# d11toy2.net
KiCad netlist of a schematic drawn in EAGLE
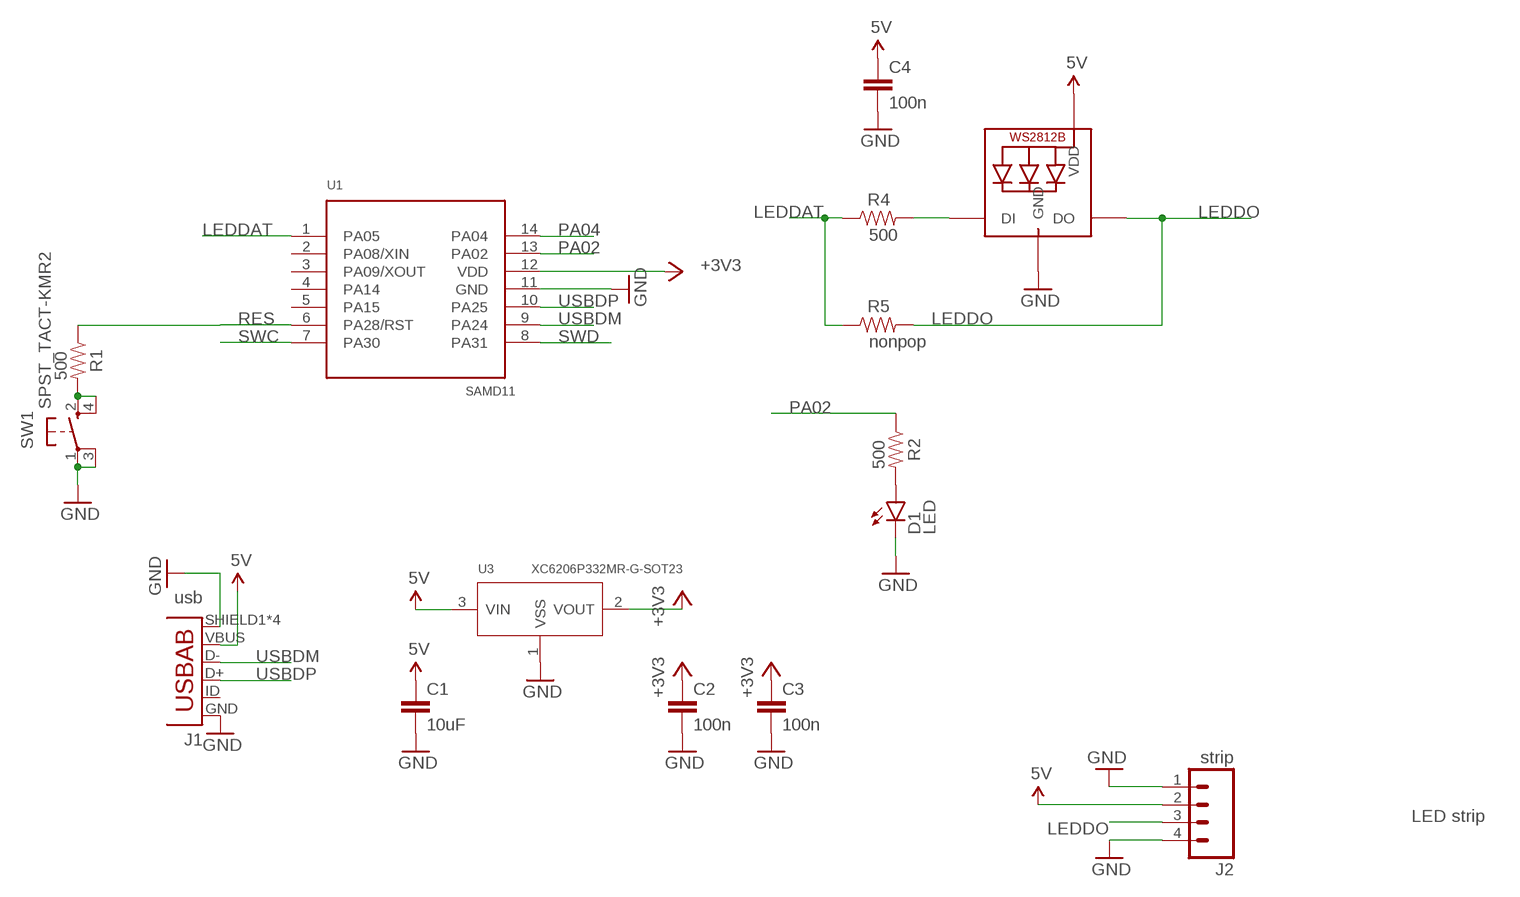
[diagram p0: schematic, sheet 1]

(export (version "E")
  (design (tool "Eeschema 10.0.6"))
  (components
    (comp (ref "C1")
      (value "10uF")
      (footprint "eagle-import:0603-CAP")
      (libsource (lib "eagle-import") (part "CAP0603-CAP"))
    )
    (comp (ref "C2")
      (value "100n")
      (footprint "eagle-import:0603-CAP")
      (libsource (lib "eagle-import") (part "CAP0603-CAP"))
    )
    (comp (ref "C3")
      (value "100n")
      (footprint "eagle-import:0603-CAP")
      (libsource (lib "eagle-import") (part "CAP0603-CAP"))
    )
    (comp (ref "C4")
      (value "100n")
      (footprint "eagle-import:0603-CAP")
      (libsource (lib "eagle-import") (part "CAP0603-CAP"))
    )
    (comp (ref "D1")
      (value "LED")
      (footprint "eagle-import:LED-0603")
      (libsource (lib "eagle-import") (part "LED0603"))
    )
    (comp (ref "J1")
      (value "usb")
      (footprint "eagle-import:USB-AB-MICRO-SMD")
      (libsource (lib "eagle-import") (part "USB-AB"))
    )
    (comp (ref "J2")
      (value "strip")
      (footprint "eagle-import:1X04_NO_SILK_ALL_ROUND")
      (libsource (lib "eagle-import") (part "M04NO_SILK_ALL_ROUND"))
    )
    (comp (ref "LED1")
      (value "WS2812B5050")
      (footprint "eagle-import:WS2812B")
      (libsource (lib "eagle-import") (part "WS2812B5050"))
    )
    (comp (ref "R1")
      (value "500")
      (footprint "eagle-import:0603-RES")
      (libsource (lib "eagle-import") (part "RESISTOR0603-RES"))
    )
    (comp (ref "R2")
      (value "500")
      (footprint "eagle-import:0603-RES")
      (libsource (lib "eagle-import") (part "RESISTOR0603-RES"))
    )
    (comp (ref "R4")
      (value "500")
      (footprint "eagle-import:0603-RES")
      (libsource (lib "eagle-import") (part "RESISTOR0603-RES"))
    )
    (comp (ref "R5")
      (value "nonpop")
      (footprint "eagle-import:0603-RES")
      (libsource (lib "eagle-import") (part "RESISTOR0603-RES"))
    )
    (comp (ref "SW1")
      (value "SPST_TACT-KMR2")
      (footprint "eagle-import:KMR2")
      (libsource (lib "eagle-import") (part "SPST_TACT-KMR2"))
    )
    (comp (ref "U1")
      (value "SAMD11")
      (footprint "eagle-import:SO14")
      (libsource (lib "eagle-import") (part "SAMD11C14"))
    )
    (comp (ref "U3")
      (value "XC6206P332MR-G-SOT23")
      (footprint "eagle-import:SOT-23")
      (fields (field (name "MPN") "XC6206P332MR-G"))
      (libsource (lib "eagle-import") (part "PMIC-LDO-XC6206P332MR-G(SOT23)"))
    )
  )
  (nets
    (net (code "1") (name "+3V3") (class "Default")
      (node (ref "C2") (pin "1") (pinfunction "1_1") (pintype "passive"))
      (node (ref "C3") (pin "1") (pinfunction "1_1") (pintype "passive"))
      (node (ref "U1") (pin "12") (pinfunction "VDD_12") (pintype "bidirectional"))
      (node (ref "U3") (pin "2") (pinfunction "VOUT_2") (pintype "output"))
    )
    (net (code "2") (name "/LEDDAT") (class "Default")
      (node (ref "R4") (pin "1") (pinfunction "1_1") (pintype "passive"))
      (node (ref "R5") (pin "1") (pinfunction "1_1") (pintype "passive"))
      (node (ref "U1") (pin "1") (pinfunction "PA05_1") (pintype "bidirectional"))
    )
    (net (code "3") (name "/LEDDO") (class "Default")
      (node (ref "J2") (pin "3") (pinfunction "3_3") (pintype "passive"))
      (node (ref "LED1") (pin "2-DOUT") (pinfunction "DO_2-DOUT") (pintype "output"))
      (node (ref "R5") (pin "2") (pinfunction "2_2") (pintype "passive"))
    )
    (net (code "4") (name "/PA02") (class "Default")
      (node (ref "R2") (pin "1") (pinfunction "1_1") (pintype "passive"))
      (node (ref "U1") (pin "13") (pinfunction "PA02_13") (pintype "bidirectional"))
    )
    (net (code "5") (name "/PA04") (class "Default")
      (node (ref "U1") (pin "14") (pinfunction "PA04_14") (pintype "bidirectional"))
    )
    (net (code "6") (name "/RES") (class "Default")
      (node (ref "R1") (pin "1") (pinfunction "1_1") (pintype "passive"))
      (node (ref "U1") (pin "6") (pinfunction "PA28/RST_6") (pintype "bidirectional"))
    )
    (net (code "7") (name "/SWC") (class "Default")
      (node (ref "U1") (pin "7") (pinfunction "PA30_7") (pintype "bidirectional"))
    )
    (net (code "8") (name "/SWD") (class "Default")
      (node (ref "U1") (pin "8") (pinfunction "PA31_8") (pintype "bidirectional"))
    )
    (net (code "9") (name "/USBDM") (class "Default")
      (node (ref "J1") (pin "D-") (pinfunction "D-_D-") (pintype "bidirectional"))
      (node (ref "U1") (pin "9") (pinfunction "PA24_9") (pintype "bidirectional"))
    )
    (net (code "10") (name "/USBDP") (class "Default")
      (node (ref "J1") (pin "D+") (pinfunction "D+_D+") (pintype "bidirectional"))
      (node (ref "U1") (pin "10") (pinfunction "PA25_10") (pintype "bidirectional"))
    )
    (net (code "11") (name "5V") (class "Default")
      (node (ref "C1") (pin "1") (pinfunction "1_1") (pintype "passive"))
      (node (ref "C4") (pin "1") (pinfunction "1_1") (pintype "passive"))
      (node (ref "J1") (pin "VBUS") (pinfunction "VBUS_VBUS") (pintype "bidirectional"))
      (node (ref "J2") (pin "2") (pinfunction "2_2") (pintype "passive"))
      (node (ref "LED1") (pin "1-VDD") (pinfunction "VDD_1-VDD") (pintype "power_in"))
      (node (ref "U3") (pin "3") (pinfunction "VIN_3") (pintype "input"))
    )
    (net (code "12") (name "GND") (class "Default")
      (node (ref "C1") (pin "2") (pinfunction "2_2") (pintype "passive"))
      (node (ref "C2") (pin "2") (pinfunction "2_2") (pintype "passive"))
      (node (ref "C3") (pin "2") (pinfunction "2_2") (pintype "passive"))
      (node (ref "C4") (pin "2") (pinfunction "2_2") (pintype "passive"))
      (node (ref "D1") (pin "C") (pinfunction "C_C") (pintype "passive"))
      (node (ref "J1") (pin "GND") (pinfunction "GND_GND") (pintype "bidirectional"))
      (node (ref "J1") (pin "SHIELD1") (pinfunction "SHIELD_SHIELD1") (pintype "bidirectional"))
      (node (ref "J1") (pin "SHIELD2") (pinfunction "SHIELD_SHIELD2") (pintype "bidirectional"))
      (node (ref "J1") (pin "SHIELD3") (pinfunction "SHIELD_SHIELD3") (pintype "bidirectional"))
      (node (ref "J1") (pin "SHIELD4") (pinfunction "SHIELD_SHIELD4") (pintype "bidirectional"))
      (node (ref "J2") (pin "1") (pinfunction "1_1") (pintype "passive"))
      (node (ref "J2") (pin "4") (pinfunction "4_4") (pintype "passive"))
      (node (ref "LED1") (pin "3-GND") (pinfunction "GND_3-GND") (pintype "power_in"))
      (node (ref "SW1") (pin "1") (pinfunction "P_1") (pintype "passive"))
      (node (ref "SW1") (pin "3") (pinfunction "P1_3") (pintype "passive"))
      (node (ref "U1") (pin "11") (pinfunction "GND_11") (pintype "bidirectional"))
      (node (ref "U3") (pin "1") (pinfunction "VSS_1") (pintype "power_in"))
    )
    (net (code "13") (name "Net-(D1-PadA)") (class "Default")
      (node (ref "D1") (pin "A") (pinfunction "A_A") (pintype "passive"))
      (node (ref "R2") (pin "2") (pinfunction "2_2") (pintype "passive"))
    )
    (net (code "14") (name "Net-(LED1-DI)") (class "Default")
      (node (ref "LED1") (pin "4-DIN") (pinfunction "DI_4-DIN") (pintype "input"))
      (node (ref "R4") (pin "2") (pinfunction "2_2") (pintype "passive"))
    )
    (net (code "15") (name "Net-(SW1-S)") (class "Default")
      (node (ref "R1") (pin "2") (pinfunction "2_2") (pintype "passive"))
      (node (ref "SW1") (pin "2") (pinfunction "S_2") (pintype "passive"))
      (node (ref "SW1") (pin "4") (pinfunction "S1_4") (pintype "passive"))
    )
    (net (code "16") (name "unconnected-(J1-USBID-PadID)") (class "Default")
      (node (ref "J1") (pin "ID") (pinfunction "USBID_ID") (pintype "bidirectional"))
    )
    (net (code "17") (name "unconnected-(U1-PA08{slash}XIN-Pad2)") (class "Default")
      (node (ref "U1") (pin "2") (pinfunction "PA08/XIN_2") (pintype "bidirectional"))
    )
    (net (code "18") (name "unconnected-(U1-PA09{slash}XOUT-Pad3)") (class "Default")
      (node (ref "U1") (pin "3") (pinfunction "PA09/XOUT_3") (pintype "bidirectional"))
    )
    (net (code "19") (name "unconnected-(U1-PA14-Pad4)") (class "Default")
      (node (ref "U1") (pin "4") (pinfunction "PA14_4") (pintype "bidirectional"))
    )
    (net (code "20") (name "unconnected-(U1-PA15-Pad5)") (class "Default")
      (node (ref "U1") (pin "5") (pinfunction "PA15_5") (pintype "bidirectional"))
    )
  )
)
